# ADC.net
KiCad netlist of a schematic drawn in Altium Designer
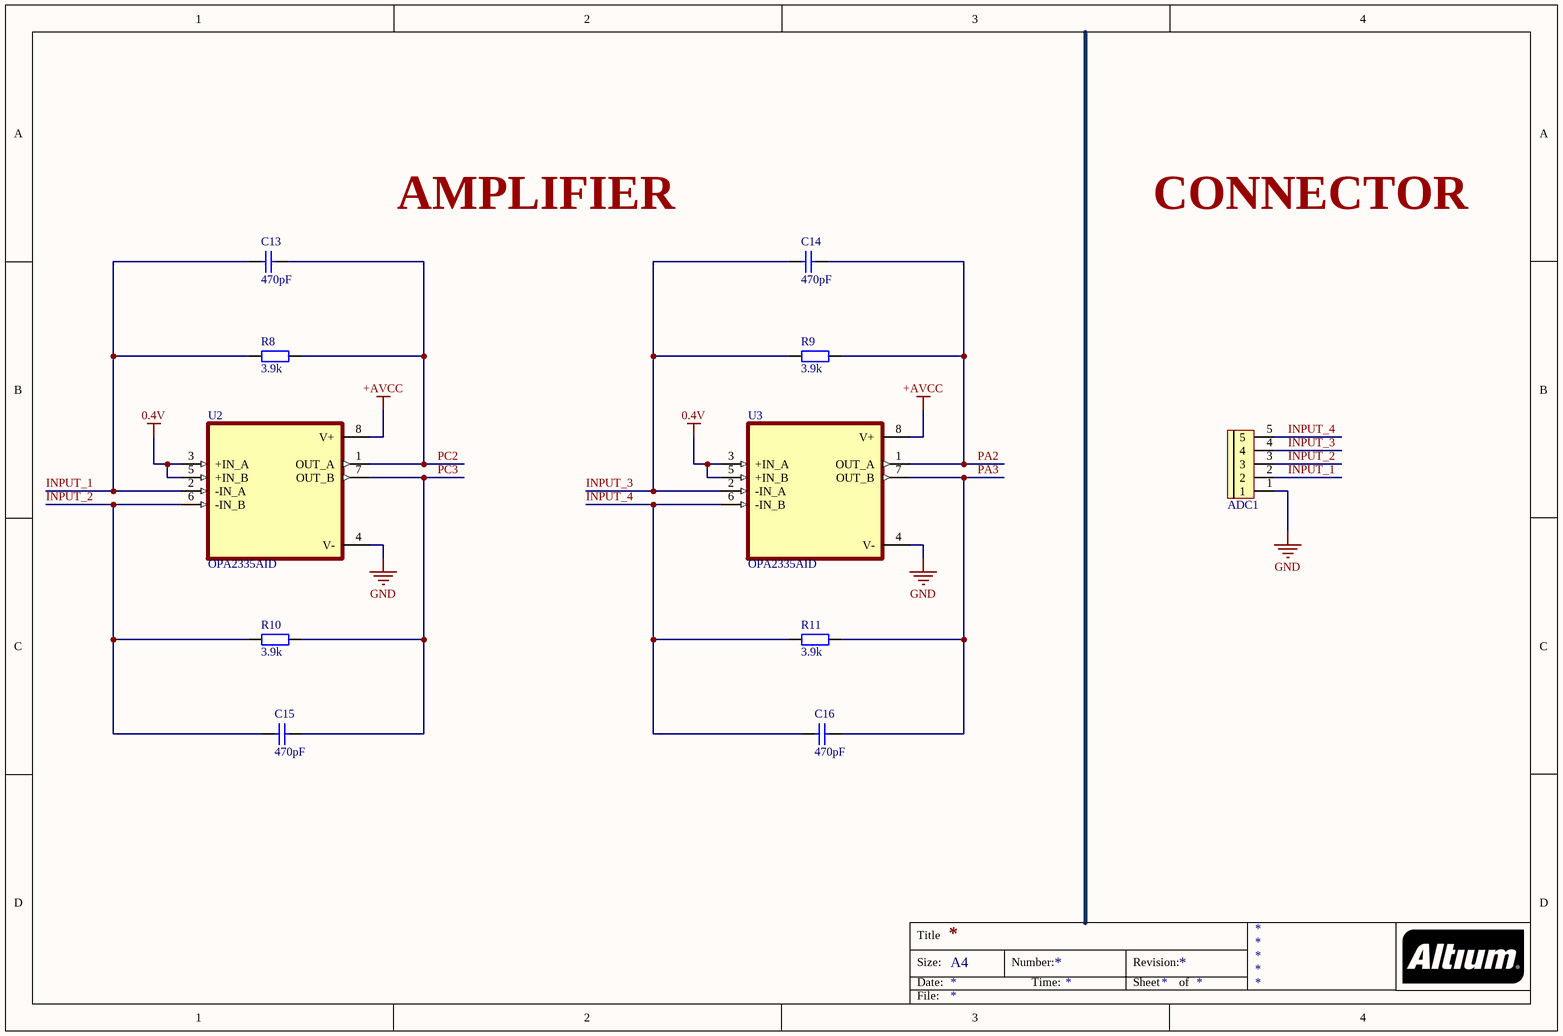
[diagram p0: ADC.SchDoc]

(export (version "E")
  (design (tool "Eeschema 10.0.6"))
  (components
    (comp (ref "ADC1")
      (value "CON 5 EDG5.08")
      (footprint "CON 5 5EDG5.08")
      (description "Cắm")
      (libsource (lib "Altium_Lib_by_KhueNguyenCreator") (part "CON 5 EDG5.08"))
    )
    (comp (ref "C13")
      (value "470pF")
      (footprint "tu 0603")
      (description "Dán")
      (libsource (lib "Altium_Lib_by_KhueNguyenCreator") (part "Tu 0603 470pF 50V 10%"))
    )
    (comp (ref "C14")
      (value "470pF")
      (footprint "tu 0603")
      (description "Dán")
      (libsource (lib "Altium_Lib_by_KhueNguyenCreator") (part "Tu 0603 470pF 50V 10%"))
    )
    (comp (ref "C15")
      (value "470pF")
      (footprint "tu 0603")
      (description "Dán")
      (libsource (lib "Altium_Lib_by_KhueNguyenCreator") (part "Tu 0603 470pF 50V 10%"))
    )
    (comp (ref "C16")
      (value "470pF")
      (footprint "tu 0603")
      (description "Dán")
      (libsource (lib "Altium_Lib_by_KhueNguyenCreator") (part "Tu 0603 470pF 50V 10%"))
    )
    (comp (ref "R8")
      (value "3.9k")
      (footprint "tro smd 0603")
      (description "Dán")
      (libsource (lib "Altium_Lib_by_KhueNguyenCreator") (part "Tro 0603 1% 3.9k"))
    )
    (comp (ref "R9")
      (value "3.9k")
      (footprint "tro smd 0603")
      (description "Dán")
      (libsource (lib "Altium_Lib_by_KhueNguyenCreator") (part "Tro 0603 1% 3.9k"))
    )
    (comp (ref "R10")
      (value "3.9k")
      (footprint "tro smd 0603")
      (description "Dán")
      (libsource (lib "Altium_Lib_by_KhueNguyenCreator") (part "Tro 0603 1% 3.9k"))
    )
    (comp (ref "R11")
      (value "3.9k")
      (footprint "tro smd 0603")
      (description "Dán")
      (libsource (lib "Altium_Lib_by_KhueNguyenCreator") (part "Tro 0603 1% 3.9k"))
    )
    (comp (ref "U2")
      (value "OPA2335AID")
      (footprint "SOIC127P599X175-8N")
      (fields (field (name "MF") "{'manufacturer': u'Texas Instruments'}"))
      (libsource (lib "SnapEDA_Library") (part "OPA2335AID"))
    )
    (comp (ref "U3")
      (value "OPA2335AID")
      (footprint "SOIC127P599X175-8N")
      (fields (field (name "MF") "{'manufacturer': u'Texas Instruments'}"))
      (libsource (lib "SnapEDA_Library") (part "OPA2335AID"))
    )
  )
  (nets
    (net (code "1") (name "+AVCC") (class "Default")
      (node (ref "U2") (pin "8") (pinfunction "V+_8") (pintype "power_in"))
      (node (ref "U3") (pin "8") (pinfunction "V+_8") (pintype "power_in"))
    )
    (net (code "2") (name "/INPUT_1") (class "Default")
      (node (ref "ADC1") (pin "2") (pinfunction "2_2") (pintype "passive"))
      (node (ref "C13") (pin "2") (pinfunction "2_2") (pintype "passive"))
      (node (ref "R8") (pin "1") (pinfunction "1_1") (pintype "passive"))
      (node (ref "U2") (pin "2") (pinfunction "-IN_A_2") (pintype "input"))
    )
    (net (code "3") (name "/INPUT_2") (class "Default")
      (node (ref "ADC1") (pin "3") (pinfunction "3_3") (pintype "passive"))
      (node (ref "C15") (pin "2") (pinfunction "2_2") (pintype "passive"))
      (node (ref "R10") (pin "1") (pinfunction "1_1") (pintype "passive"))
      (node (ref "U2") (pin "6") (pinfunction "-IN_B_6") (pintype "input"))
    )
    (net (code "4") (name "/INPUT_3") (class "Default")
      (node (ref "ADC1") (pin "4") (pinfunction "4_4") (pintype "passive"))
      (node (ref "C14") (pin "2") (pinfunction "2_2") (pintype "passive"))
      (node (ref "R9") (pin "1") (pinfunction "1_1") (pintype "passive"))
      (node (ref "U3") (pin "2") (pinfunction "-IN_A_2") (pintype "input"))
    )
    (net (code "5") (name "/INPUT_4") (class "Default")
      (node (ref "ADC1") (pin "5") (pinfunction "5_5") (pintype "passive"))
      (node (ref "C16") (pin "2") (pinfunction "2_2") (pintype "passive"))
      (node (ref "R11") (pin "1") (pinfunction "1_1") (pintype "passive"))
      (node (ref "U3") (pin "6") (pinfunction "-IN_B_6") (pintype "input"))
    )
    (net (code "6") (name "/PA2") (class "Default")
      (node (ref "C14") (pin "1") (pinfunction "1_1") (pintype "passive"))
      (node (ref "R9") (pin "2") (pinfunction "2_2") (pintype "passive"))
      (node (ref "U3") (pin "1") (pinfunction "OUT_A_1") (pintype "output"))
    )
    (net (code "7") (name "/PA3") (class "Default")
      (node (ref "C16") (pin "1") (pinfunction "1_1") (pintype "passive"))
      (node (ref "R11") (pin "2") (pinfunction "2_2") (pintype "passive"))
      (node (ref "U3") (pin "7") (pinfunction "OUT_B_7") (pintype "output"))
    )
    (net (code "8") (name "/PC2") (class "Default")
      (node (ref "C13") (pin "1") (pinfunction "1_1") (pintype "passive"))
      (node (ref "R8") (pin "2") (pinfunction "2_2") (pintype "passive"))
      (node (ref "U2") (pin "1") (pinfunction "OUT_A_1") (pintype "output"))
    )
    (net (code "9") (name "/PC3") (class "Default")
      (node (ref "C15") (pin "1") (pinfunction "1_1") (pintype "passive"))
      (node (ref "R10") (pin "2") (pinfunction "2_2") (pintype "passive"))
      (node (ref "U2") (pin "7") (pinfunction "OUT_B_7") (pintype "output"))
    )
    (net (code "10") (name "0.4V") (class "Default")
      (node (ref "U2") (pin "3") (pinfunction "+IN_A_3") (pintype "input"))
      (node (ref "U2") (pin "5") (pinfunction "+IN_B_5") (pintype "input"))
      (node (ref "U3") (pin "3") (pinfunction "+IN_A_3") (pintype "input"))
      (node (ref "U3") (pin "5") (pinfunction "+IN_B_5") (pintype "input"))
    )
    (net (code "11") (name "GND") (class "Default")
      (node (ref "ADC1") (pin "1") (pinfunction "1_1") (pintype "passive"))
      (node (ref "U2") (pin "4") (pinfunction "V-_4") (pintype "power_in"))
      (node (ref "U3") (pin "4") (pinfunction "V-_4") (pintype "power_in"))
    )
  )
)
